# Schematic.net
KiCad netlist of a schematic drawn in EAGLE
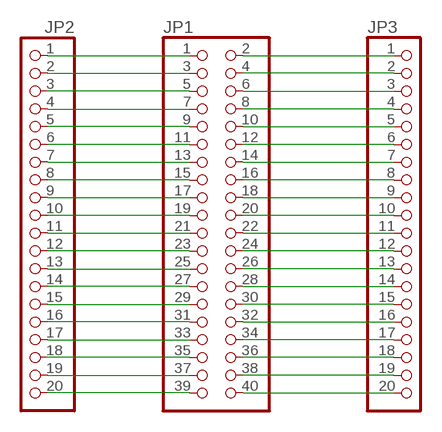
[diagram p0: schematic, sheet 1]

(export (version "E")
  (design (tool "Eeschema 10.0.6"))
  (components
    (comp (ref "JP1")
      (value "PINHD-2X20")
      (footprint "eagle-import:2X20")
      (libsource (lib "eagle-import") (part "PINHD-2X20"))
    )
    (comp (ref "JP2")
      (value "PINHD-1X20")
      (footprint "eagle-import:1X20")
      (libsource (lib "eagle-import") (part "PINHD-1X20"))
    )
    (comp (ref "JP3")
      (value "PINHD-1X20")
      (footprint "eagle-import:1X20")
      (libsource (lib "eagle-import") (part "PINHD-1X20"))
    )
  )
  (nets
    (net (code "1") (name "Net-(JP1-Pad1)") (class "Default")
      (node (ref "JP1") (pin "1") (pinfunction "1_1") (pintype "passive"))
      (node (ref "JP2") (pin "1") (pinfunction "1_1") (pintype "passive"))
    )
    (net (code "2") (name "Net-(JP1-Pad2)") (class "Default")
      (node (ref "JP1") (pin "2") (pinfunction "2_2") (pintype "passive"))
      (node (ref "JP3") (pin "1") (pinfunction "1_1") (pintype "passive"))
    )
    (net (code "3") (name "Net-(JP1-Pad3)") (class "Default")
      (node (ref "JP1") (pin "3") (pinfunction "3_3") (pintype "passive"))
      (node (ref "JP2") (pin "2") (pinfunction "2_2") (pintype "passive"))
    )
    (net (code "4") (name "Net-(JP1-Pad4)") (class "Default")
      (node (ref "JP1") (pin "4") (pinfunction "4_4") (pintype "passive"))
      (node (ref "JP3") (pin "2") (pinfunction "2_2") (pintype "passive"))
    )
    (net (code "5") (name "Net-(JP1-Pad5)") (class "Default")
      (node (ref "JP1") (pin "5") (pinfunction "5_5") (pintype "passive"))
      (node (ref "JP2") (pin "3") (pinfunction "3_3") (pintype "passive"))
    )
    (net (code "6") (name "Net-(JP1-Pad6)") (class "Default")
      (node (ref "JP1") (pin "6") (pinfunction "6_6") (pintype "passive"))
      (node (ref "JP3") (pin "3") (pinfunction "3_3") (pintype "passive"))
    )
    (net (code "7") (name "Net-(JP1-Pad7)") (class "Default")
      (node (ref "JP1") (pin "7") (pinfunction "7_7") (pintype "passive"))
      (node (ref "JP2") (pin "4") (pinfunction "4_4") (pintype "passive"))
    )
    (net (code "8") (name "Net-(JP1-Pad8)") (class "Default")
      (node (ref "JP1") (pin "8") (pinfunction "8_8") (pintype "passive"))
      (node (ref "JP3") (pin "4") (pinfunction "4_4") (pintype "passive"))
    )
    (net (code "9") (name "Net-(JP1-Pad9)") (class "Default")
      (node (ref "JP1") (pin "9") (pinfunction "9_9") (pintype "passive"))
      (node (ref "JP2") (pin "5") (pinfunction "5_5") (pintype "passive"))
    )
    (net (code "10") (name "Net-(JP1-Pad10)") (class "Default")
      (node (ref "JP1") (pin "10") (pinfunction "10_10") (pintype "passive"))
      (node (ref "JP3") (pin "5") (pinfunction "5_5") (pintype "passive"))
    )
    (net (code "11") (name "Net-(JP1-Pad11)") (class "Default")
      (node (ref "JP1") (pin "11") (pinfunction "11_11") (pintype "passive"))
      (node (ref "JP2") (pin "6") (pinfunction "6_6") (pintype "passive"))
    )
    (net (code "12") (name "Net-(JP1-Pad12)") (class "Default")
      (node (ref "JP1") (pin "12") (pinfunction "12_12") (pintype "passive"))
      (node (ref "JP3") (pin "6") (pinfunction "6_6") (pintype "passive"))
    )
    (net (code "13") (name "Net-(JP1-Pad13)") (class "Default")
      (node (ref "JP1") (pin "13") (pinfunction "13_13") (pintype "passive"))
      (node (ref "JP2") (pin "7") (pinfunction "7_7") (pintype "passive"))
    )
    (net (code "14") (name "Net-(JP1-Pad14)") (class "Default")
      (node (ref "JP1") (pin "14") (pinfunction "14_14") (pintype "passive"))
      (node (ref "JP3") (pin "7") (pinfunction "7_7") (pintype "passive"))
    )
    (net (code "15") (name "Net-(JP1-Pad15)") (class "Default")
      (node (ref "JP1") (pin "15") (pinfunction "15_15") (pintype "passive"))
      (node (ref "JP2") (pin "8") (pinfunction "8_8") (pintype "passive"))
    )
    (net (code "16") (name "Net-(JP1-Pad16)") (class "Default")
      (node (ref "JP1") (pin "16") (pinfunction "16_16") (pintype "passive"))
      (node (ref "JP3") (pin "8") (pinfunction "8_8") (pintype "passive"))
    )
    (net (code "17") (name "Net-(JP1-Pad17)") (class "Default")
      (node (ref "JP1") (pin "17") (pinfunction "17_17") (pintype "passive"))
      (node (ref "JP2") (pin "9") (pinfunction "9_9") (pintype "passive"))
    )
    (net (code "18") (name "Net-(JP1-Pad18)") (class "Default")
      (node (ref "JP1") (pin "18") (pinfunction "18_18") (pintype "passive"))
      (node (ref "JP3") (pin "9") (pinfunction "9_9") (pintype "passive"))
    )
    (net (code "19") (name "Net-(JP1-Pad19)") (class "Default")
      (node (ref "JP1") (pin "19") (pinfunction "19_19") (pintype "passive"))
      (node (ref "JP2") (pin "10") (pinfunction "10_10") (pintype "passive"))
    )
    (net (code "20") (name "Net-(JP1-Pad20)") (class "Default")
      (node (ref "JP1") (pin "20") (pinfunction "20_20") (pintype "passive"))
      (node (ref "JP3") (pin "10") (pinfunction "10_10") (pintype "passive"))
    )
    (net (code "21") (name "Net-(JP1-Pad21)") (class "Default")
      (node (ref "JP1") (pin "21") (pinfunction "21_21") (pintype "passive"))
      (node (ref "JP2") (pin "11") (pinfunction "11_11") (pintype "passive"))
    )
    (net (code "22") (name "Net-(JP1-Pad22)") (class "Default")
      (node (ref "JP1") (pin "22") (pinfunction "22_22") (pintype "passive"))
      (node (ref "JP3") (pin "11") (pinfunction "11_11") (pintype "passive"))
    )
    (net (code "23") (name "Net-(JP1-Pad23)") (class "Default")
      (node (ref "JP1") (pin "23") (pinfunction "23_23") (pintype "passive"))
      (node (ref "JP2") (pin "12") (pinfunction "12_12") (pintype "passive"))
    )
    (net (code "24") (name "Net-(JP1-Pad24)") (class "Default")
      (node (ref "JP1") (pin "24") (pinfunction "24_24") (pintype "passive"))
      (node (ref "JP3") (pin "12") (pinfunction "12_12") (pintype "passive"))
    )
    (net (code "25") (name "Net-(JP1-Pad25)") (class "Default")
      (node (ref "JP1") (pin "25") (pinfunction "25_25") (pintype "passive"))
      (node (ref "JP2") (pin "13") (pinfunction "13_13") (pintype "passive"))
    )
    (net (code "26") (name "Net-(JP1-Pad26)") (class "Default")
      (node (ref "JP1") (pin "26") (pinfunction "26_26") (pintype "passive"))
      (node (ref "JP3") (pin "13") (pinfunction "13_13") (pintype "passive"))
    )
    (net (code "27") (name "Net-(JP1-Pad27)") (class "Default")
      (node (ref "JP1") (pin "27") (pinfunction "27_27") (pintype "passive"))
      (node (ref "JP2") (pin "14") (pinfunction "14_14") (pintype "passive"))
    )
    (net (code "28") (name "Net-(JP1-Pad28)") (class "Default")
      (node (ref "JP1") (pin "28") (pinfunction "28_28") (pintype "passive"))
      (node (ref "JP3") (pin "14") (pinfunction "14_14") (pintype "passive"))
    )
    (net (code "29") (name "Net-(JP1-Pad29)") (class "Default")
      (node (ref "JP1") (pin "29") (pinfunction "29_29") (pintype "passive"))
      (node (ref "JP2") (pin "15") (pinfunction "15_15") (pintype "passive"))
    )
    (net (code "30") (name "Net-(JP1-Pad30)") (class "Default")
      (node (ref "JP1") (pin "30") (pinfunction "30_30") (pintype "passive"))
      (node (ref "JP3") (pin "15") (pinfunction "15_15") (pintype "passive"))
    )
    (net (code "31") (name "Net-(JP1-Pad31)") (class "Default")
      (node (ref "JP1") (pin "31") (pinfunction "31_31") (pintype "passive"))
      (node (ref "JP2") (pin "16") (pinfunction "16_16") (pintype "passive"))
    )
    (net (code "32") (name "Net-(JP1-Pad32)") (class "Default")
      (node (ref "JP1") (pin "32") (pinfunction "32_32") (pintype "passive"))
      (node (ref "JP3") (pin "16") (pinfunction "16_16") (pintype "passive"))
    )
    (net (code "33") (name "Net-(JP1-Pad33)") (class "Default")
      (node (ref "JP1") (pin "33") (pinfunction "33_33") (pintype "passive"))
      (node (ref "JP2") (pin "17") (pinfunction "17_17") (pintype "passive"))
    )
    (net (code "34") (name "Net-(JP1-Pad34)") (class "Default")
      (node (ref "JP1") (pin "34") (pinfunction "34_34") (pintype "passive"))
      (node (ref "JP3") (pin "17") (pinfunction "17_17") (pintype "passive"))
    )
    (net (code "35") (name "Net-(JP1-Pad35)") (class "Default")
      (node (ref "JP1") (pin "35") (pinfunction "35_35") (pintype "passive"))
      (node (ref "JP2") (pin "18") (pinfunction "18_18") (pintype "passive"))
    )
    (net (code "36") (name "Net-(JP1-Pad36)") (class "Default")
      (node (ref "JP1") (pin "36") (pinfunction "36_36") (pintype "passive"))
      (node (ref "JP3") (pin "18") (pinfunction "18_18") (pintype "passive"))
    )
    (net (code "37") (name "Net-(JP1-Pad37)") (class "Default")
      (node (ref "JP1") (pin "37") (pinfunction "37_37") (pintype "passive"))
      (node (ref "JP2") (pin "19") (pinfunction "19_19") (pintype "passive"))
    )
    (net (code "38") (name "Net-(JP1-Pad38)") (class "Default")
      (node (ref "JP1") (pin "38") (pinfunction "38_38") (pintype "passive"))
      (node (ref "JP3") (pin "19") (pinfunction "19_19") (pintype "passive"))
    )
    (net (code "39") (name "Net-(JP1-Pad39)") (class "Default")
      (node (ref "JP1") (pin "39") (pinfunction "39_39") (pintype "passive"))
      (node (ref "JP2") (pin "20") (pinfunction "20_20") (pintype "passive"))
    )
    (net (code "40") (name "Net-(JP1-Pad40)") (class "Default")
      (node (ref "JP1") (pin "40") (pinfunction "40_40") (pintype "passive"))
      (node (ref "JP3") (pin "20") (pinfunction "20_20") (pintype "passive"))
    )
  )
)
